# 2LD-17-mk-1_3.net
KiCad netlist of a schematic drawn in EAGLE
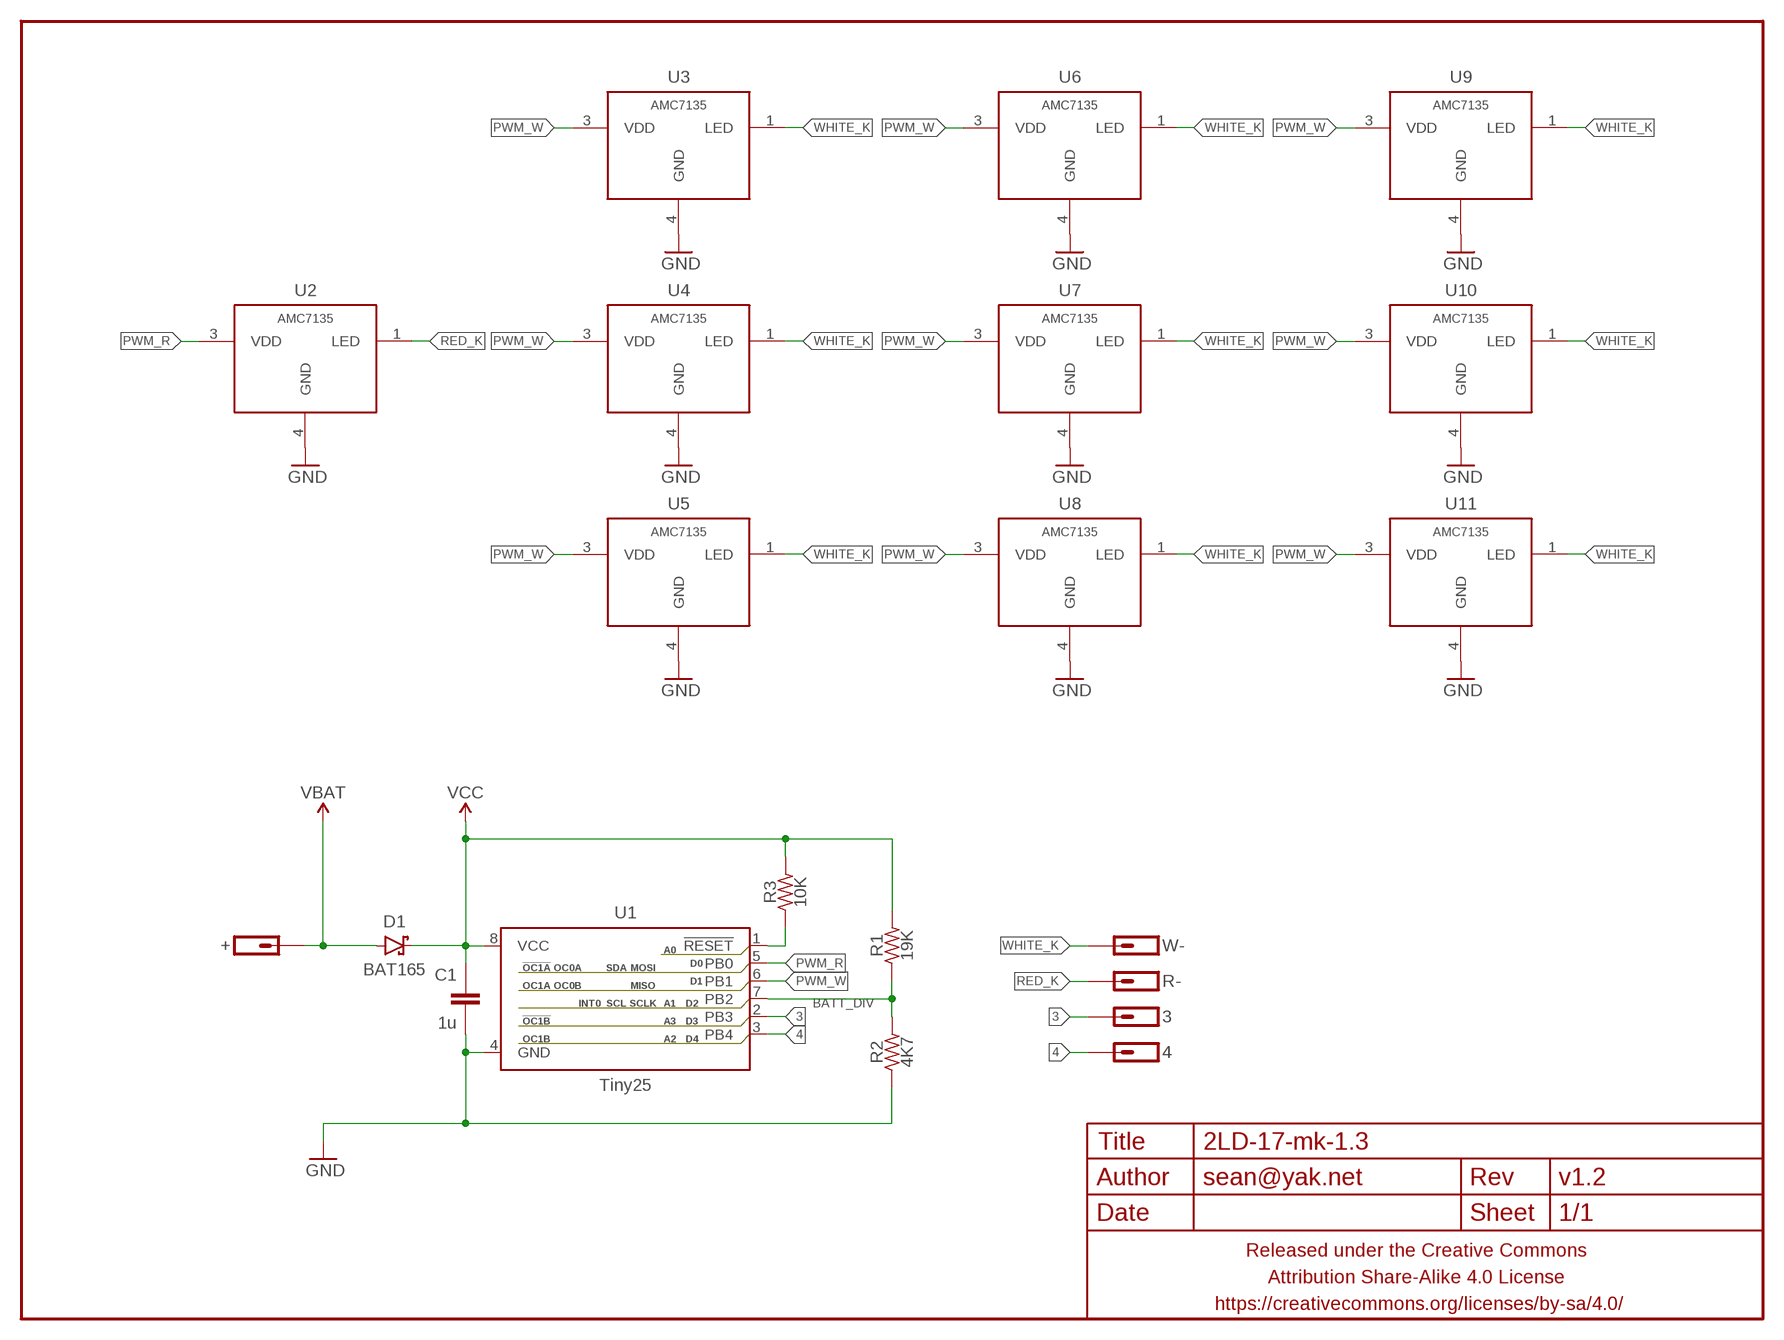
[diagram p0: schematic, sheet 1]

(export (version "E")
  (design (tool "Eeschema 10.0.6"))
  (components
    (comp (ref "+")
      (value "M01PTH-1.2MM-NS")
      (footprint "eagle-import:1X01-1.2MM-NS")
      (libsource (lib "eagle-import") (part "M01PTH-1.2MM-NS"))
    )
    (comp (ref "3")
      (value "M01SMD-1MM-DIA-NS")
      (footprint "eagle-import:1X01-SMD-1MM-DIA-NS")
      (libsource (lib "eagle-import") (part "M01SMD-1MM-DIA-NS"))
    )
    (comp (ref "4")
      (value "M01SMD-1MM-DIA-NS")
      (footprint "eagle-import:1X01-SMD-1MM-DIA-NS")
      (libsource (lib "eagle-import") (part "M01SMD-1MM-DIA-NS"))
    )
    (comp (ref "C1")
      (value "1u")
      (footprint "eagle-import:C0402")
      (libsource (lib "eagle-import") (part "CAPACITOR-CERAMICC0402"))
    )
    (comp (ref "D1")
      (value "BAT165")
      (footprint "eagle-import:SOD323-SCHOTTKY")
      (libsource (lib "eagle-import") (part "DIODE-SCHOTTKYSOD323"))
    )
    (comp (ref "FRAME1")
      (value "FRAME-LETTERNO_PACKAGE")
      (footprint "eagle-import:DUMMY")
      (fields (field (name "DESIGNER") "sean@yak.net") (field (name "VERSION") "v1.2"))
      (libsource (lib "eagle-import") (part "FRAME-LETTERNO_PACKAGE"))
    )
    (comp (ref "R-")
      (value "M01SMD-1MM-DIA-NS")
      (footprint "eagle-import:1X01-SMD-1MM-DIA-NS")
      (libsource (lib "eagle-import") (part "M01SMD-1MM-DIA-NS"))
    )
    (comp (ref "R1")
      (value "19K")
      (footprint "eagle-import:R0402")
      (libsource (lib "eagle-import") (part "RESISTORR0402"))
    )
    (comp (ref "R2")
      (value "4K7")
      (footprint "eagle-import:R0402")
      (libsource (lib "eagle-import") (part "RESISTORR0402"))
    )
    (comp (ref "R3")
      (value "10K")
      (footprint "eagle-import:R0402")
      (libsource (lib "eagle-import") (part "RESISTORR0402"))
    )
    (comp (ref "U1")
      (value "Tiny25")
      (footprint "eagle-import:SO08-NARROWER")
      (libsource (lib "eagle-import") (part "ATTINY13SOIC-NARROWPADS"))
    )
    (comp (ref "U2")
      (value "AMC7135")
      (footprint "eagle-import:SOT89-NOTHERM-ROUNDED-LESS")
      (libsource (lib "eagle-import") (part "AMC7135SOT-89-NOTHERM-ROUNDED-LESS"))
    )
    (comp (ref "U3")
      (value "AMC7135")
      (footprint "eagle-import:SOT89-NOTHERM-ROUNDED-LESS")
      (libsource (lib "eagle-import") (part "AMC7135SOT-89-NOTHERM-ROUNDED-LESS"))
    )
    (comp (ref "U4")
      (value "AMC7135")
      (footprint "eagle-import:SOT89-NOTHERM-ROUNDED-LESS")
      (libsource (lib "eagle-import") (part "AMC7135SOT-89-NOTHERM-ROUNDED-LESS"))
    )
    (comp (ref "U5")
      (value "AMC7135")
      (footprint "eagle-import:SOT89-NOTHERM-ROUNDED-LESS")
      (libsource (lib "eagle-import") (part "AMC7135SOT-89-NOTHERM-ROUNDED-LESS"))
    )
    (comp (ref "U6")
      (value "AMC7135")
      (footprint "eagle-import:SOT89-NOTHERM-ROUNDED-LESS")
      (libsource (lib "eagle-import") (part "AMC7135SOT-89-NOTHERM-ROUNDED-LESS"))
    )
    (comp (ref "U7")
      (value "AMC7135")
      (footprint "eagle-import:SOT89-NOTHERM-ROUNDED-LESS")
      (libsource (lib "eagle-import") (part "AMC7135SOT-89-NOTHERM-ROUNDED-LESS"))
    )
    (comp (ref "U8")
      (value "AMC7135")
      (footprint "eagle-import:SOT89-NOTHERM-ROUNDED-LESS")
      (libsource (lib "eagle-import") (part "AMC7135SOT-89-NOTHERM-ROUNDED-LESS"))
    )
    (comp (ref "U9")
      (value "AMC7135")
      (footprint "eagle-import:SOT89-NOTHERM-ROUNDED-LESS")
      (libsource (lib "eagle-import") (part "AMC7135SOT-89-NOTHERM-ROUNDED-LESS"))
    )
    (comp (ref "U10")
      (value "AMC7135")
      (footprint "eagle-import:SOT89-NOTHERM-ROUNDED-LESS")
      (libsource (lib "eagle-import") (part "AMC7135SOT-89-NOTHERM-ROUNDED-LESS"))
    )
    (comp (ref "U11")
      (value "AMC7135")
      (footprint "eagle-import:SOT89-NOTHERM-ROUNDED-LESS")
      (libsource (lib "eagle-import") (part "AMC7135SOT-89-NOTHERM-ROUNDED-LESS"))
    )
    (comp (ref "W-")
      (value "M011X01-0.9MM-CIR")
      (footprint "eagle-import:1X01-0.9MM-CIR")
      (libsource (lib "eagle-import") (part "M011X01-0.9MM-CIR"))
    )
  )
  (nets
    (net (code "1") (name "/BATT_DIV") (class "Default")
      (node (ref "R1") (pin "1") (pinfunction "1_1") (pintype "passive"))
      (node (ref "R2") (pin "2") (pinfunction "2_2") (pintype "passive"))
      (node (ref "U1") (pin "7") (pinfunction "PB2_7") (pintype "bidirectional"))
    )
    (net (code "2") (name "3") (class "Default")
      (node (ref "3") (pin "P$1") (pinfunction "1_P$1") (pintype "passive"))
      (node (ref "U1") (pin "2") (pinfunction "PB3_2") (pintype "bidirectional"))
    )
    (net (code "3") (name "4") (class "Default")
      (node (ref "4") (pin "P$1") (pinfunction "1_P$1") (pintype "passive"))
      (node (ref "U1") (pin "3") (pinfunction "PB4_3") (pintype "bidirectional"))
    )
    (net (code "4") (name "GND") (class "Default")
      (node (ref "C1") (pin "2") (pinfunction "2_2") (pintype "passive"))
      (node (ref "R2") (pin "1") (pinfunction "1_1") (pintype "passive"))
      (node (ref "U1") (pin "4") (pinfunction "GND_4") (pintype "bidirectional"))
      (node (ref "U10") (pin "4") (pinfunction "GND_4") (pintype "bidirectional"))
      (node (ref "U11") (pin "4") (pinfunction "GND_4") (pintype "bidirectional"))
      (node (ref "U2") (pin "4") (pinfunction "GND_4") (pintype "bidirectional"))
      (node (ref "U3") (pin "4") (pinfunction "GND_4") (pintype "bidirectional"))
      (node (ref "U4") (pin "4") (pinfunction "GND_4") (pintype "bidirectional"))
      (node (ref "U5") (pin "4") (pinfunction "GND_4") (pintype "bidirectional"))
      (node (ref "U6") (pin "4") (pinfunction "GND_4") (pintype "bidirectional"))
      (node (ref "U7") (pin "4") (pinfunction "GND_4") (pintype "bidirectional"))
      (node (ref "U8") (pin "4") (pinfunction "GND_4") (pintype "bidirectional"))
      (node (ref "U9") (pin "4") (pinfunction "GND_4") (pintype "bidirectional"))
    )
    (net (code "5") (name "Net-(U1-~{RESET})") (class "Default")
      (node (ref "R3") (pin "1") (pinfunction "1_1") (pintype "passive"))
      (node (ref "U1") (pin "1") (pinfunction "~{RESET}_1") (pintype "bidirectional"))
    )
    (net (code "6") (name "PWM_R") (class "Default")
      (node (ref "U1") (pin "5") (pinfunction "PB0_5") (pintype "bidirectional"))
      (node (ref "U2") (pin "3") (pinfunction "VDD_3") (pintype "bidirectional"))
    )
    (net (code "7") (name "PWM_W") (class "Default")
      (node (ref "U1") (pin "6") (pinfunction "PB1_6") (pintype "bidirectional"))
      (node (ref "U10") (pin "3") (pinfunction "VDD_3") (pintype "bidirectional"))
      (node (ref "U11") (pin "3") (pinfunction "VDD_3") (pintype "bidirectional"))
      (node (ref "U3") (pin "3") (pinfunction "VDD_3") (pintype "bidirectional"))
      (node (ref "U4") (pin "3") (pinfunction "VDD_3") (pintype "bidirectional"))
      (node (ref "U5") (pin "3") (pinfunction "VDD_3") (pintype "bidirectional"))
      (node (ref "U6") (pin "3") (pinfunction "VDD_3") (pintype "bidirectional"))
      (node (ref "U7") (pin "3") (pinfunction "VDD_3") (pintype "bidirectional"))
      (node (ref "U8") (pin "3") (pinfunction "VDD_3") (pintype "bidirectional"))
      (node (ref "U9") (pin "3") (pinfunction "VDD_3") (pintype "bidirectional"))
    )
    (net (code "8") (name "RED_K") (class "Default")
      (node (ref "R-") (pin "P$1") (pinfunction "1_P$1") (pintype "passive"))
      (node (ref "U2") (pin "1") (pinfunction "LED_1") (pintype "bidirectional"))
    )
    (net (code "9") (name "VBAT") (class "Default")
      (node (ref "+") (pin "P$1") (pinfunction "1_P$1") (pintype "passive"))
      (node (ref "D1") (pin "A") (pinfunction "A_A") (pintype "passive"))
    )
    (net (code "10") (name "VCC") (class "Default")
      (node (ref "C1") (pin "1") (pinfunction "1_1") (pintype "passive"))
      (node (ref "D1") (pin "C") (pinfunction "C_C") (pintype "passive"))
      (node (ref "R1") (pin "2") (pinfunction "2_2") (pintype "passive"))
      (node (ref "R3") (pin "2") (pinfunction "2_2") (pintype "passive"))
      (node (ref "U1") (pin "8") (pinfunction "VCC_8") (pintype "bidirectional"))
    )
    (net (code "11") (name "WHITE_K") (class "Default")
      (node (ref "U10") (pin "1") (pinfunction "LED_1") (pintype "bidirectional"))
      (node (ref "U11") (pin "1") (pinfunction "LED_1") (pintype "bidirectional"))
      (node (ref "U3") (pin "1") (pinfunction "LED_1") (pintype "bidirectional"))
      (node (ref "U4") (pin "1") (pinfunction "LED_1") (pintype "bidirectional"))
      (node (ref "U5") (pin "1") (pinfunction "LED_1") (pintype "bidirectional"))
      (node (ref "U6") (pin "1") (pinfunction "LED_1") (pintype "bidirectional"))
      (node (ref "U7") (pin "1") (pinfunction "LED_1") (pintype "bidirectional"))
      (node (ref "U8") (pin "1") (pinfunction "LED_1") (pintype "bidirectional"))
      (node (ref "U9") (pin "1") (pinfunction "LED_1") (pintype "bidirectional"))
      (node (ref "W-") (pin "P$1") (pinfunction "1_P$1") (pintype "passive"))
    )
  )
)
